# tk-retrofit.net
KiCad netlist of a schematic drawn in EAGLE
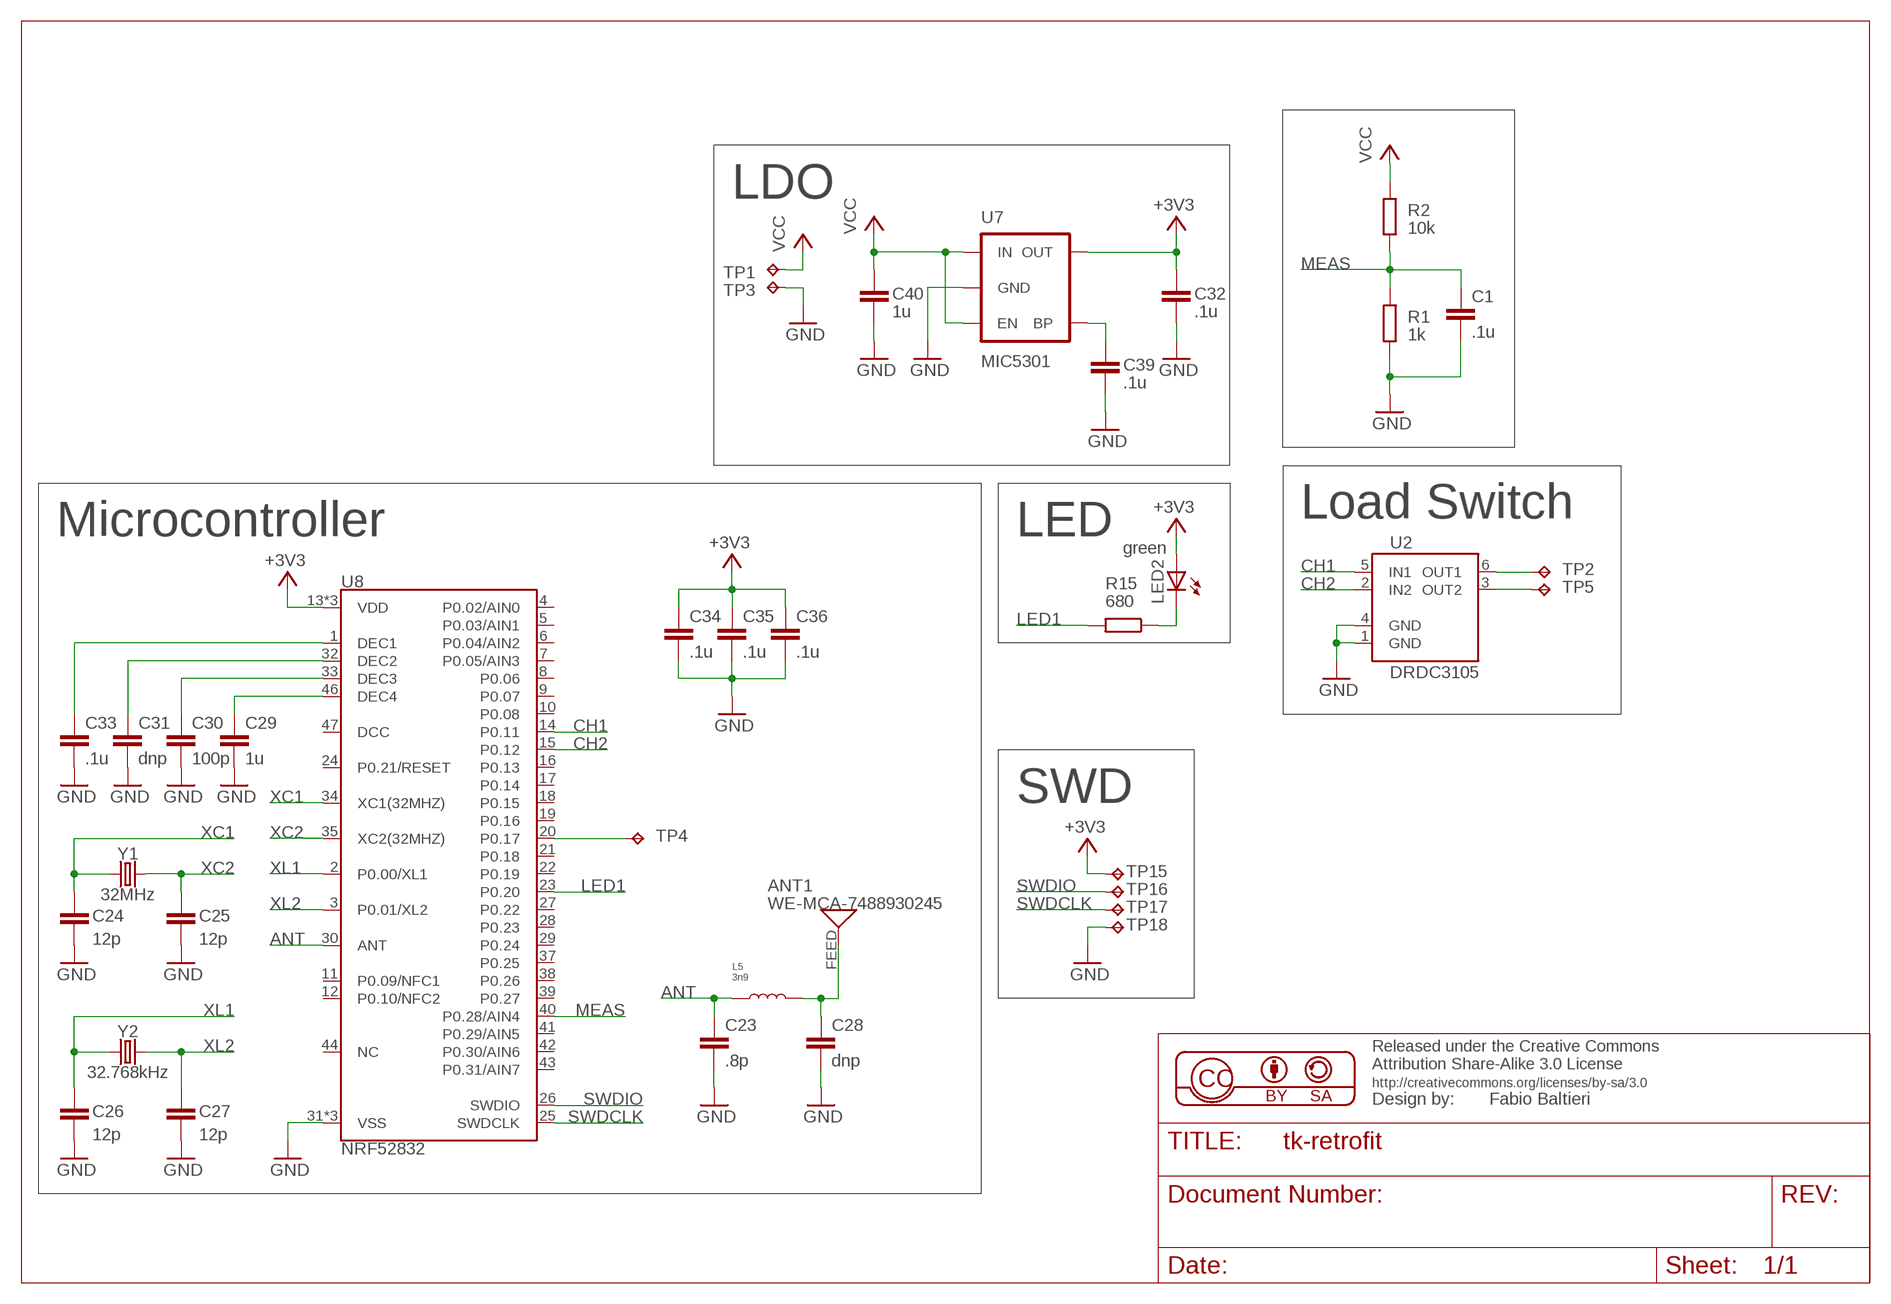
[diagram p0: schematic, sheet 1]

(export (version "E")
  (design (tool "Eeschema 10.0.6"))
  (components
    (comp (ref "ANT1")
      (value "WE-MCA-7488930245")
      (footprint "eagle-import:WE-MCA")
      (libsource (lib "eagle-import") (part "WE-MCA-7488930245"))
    )
    (comp (ref "C1")
      (value ".1u")
      (footprint "eagle-import:0603")
      (libsource (lib "eagle-import") (part "C0603"))
    )
    (comp (ref "C23")
      (value ".8p")
      (footprint "eagle-import:0603")
      (libsource (lib "eagle-import") (part "C0603"))
    )
    (comp (ref "C24")
      (value "12p")
      (footprint "eagle-import:0603")
      (libsource (lib "eagle-import") (part "C0603"))
    )
    (comp (ref "C25")
      (value "12p")
      (footprint "eagle-import:0603")
      (libsource (lib "eagle-import") (part "C0603"))
    )
    (comp (ref "C26")
      (value "12p")
      (footprint "eagle-import:0603")
      (libsource (lib "eagle-import") (part "C0603"))
    )
    (comp (ref "C27")
      (value "12p")
      (footprint "eagle-import:0603")
      (libsource (lib "eagle-import") (part "C0603"))
    )
    (comp (ref "C28")
      (value "dnp")
      (footprint "eagle-import:0603")
      (libsource (lib "eagle-import") (part "C0603"))
    )
    (comp (ref "C29")
      (value "1u")
      (footprint "eagle-import:0603")
      (libsource (lib "eagle-import") (part "C0603"))
    )
    (comp (ref "C30")
      (value "100p")
      (footprint "eagle-import:0603")
      (libsource (lib "eagle-import") (part "C0603"))
    )
    (comp (ref "C31")
      (value "dnp")
      (footprint "eagle-import:0603")
      (libsource (lib "eagle-import") (part "C0603"))
    )
    (comp (ref "C32")
      (value ".1u")
      (footprint "eagle-import:0603")
      (libsource (lib "eagle-import") (part "C0603"))
    )
    (comp (ref "C33")
      (value ".1u")
      (footprint "eagle-import:0603")
      (libsource (lib "eagle-import") (part "C0603"))
    )
    (comp (ref "C34")
      (value ".1u")
      (footprint "eagle-import:0603")
      (libsource (lib "eagle-import") (part "C0603"))
    )
    (comp (ref "C35")
      (value ".1u")
      (footprint "eagle-import:0603")
      (libsource (lib "eagle-import") (part "C0603"))
    )
    (comp (ref "C36")
      (value ".1u")
      (footprint "eagle-import:0603")
      (libsource (lib "eagle-import") (part "C0603"))
    )
    (comp (ref "C39")
      (value ".1u")
      (footprint "eagle-import:0603")
      (libsource (lib "eagle-import") (part "C0603"))
    )
    (comp (ref "C40")
      (value "1u")
      (footprint "eagle-import:0603")
      (libsource (lib "eagle-import") (part "C0603"))
    )
    (comp (ref "L5")
      (value "3n9")
      (footprint "eagle-import:L0603")
      (libsource (lib "eagle-import") (part "INDUCTOR_0603"))
    )
    (comp (ref "LED2")
      (value "LEDSML0805")
      (footprint "eagle-import:SML0805")
      (libsource (lib "eagle-import") (part "LEDSML0805"))
    )
    (comp (ref "R1")
      (value "1k")
      (footprint "eagle-import:0603")
      (libsource (lib "eagle-import") (part "R0603"))
    )
    (comp (ref "R2")
      (value "10k")
      (footprint "eagle-import:0603")
      (libsource (lib "eagle-import") (part "R0603"))
    )
    (comp (ref "R15")
      (value "680")
      (footprint "eagle-import:0603")
      (libsource (lib "eagle-import") (part "R0603"))
    )
    (comp (ref "TP1")
      (value "TPTP12R")
      (footprint "eagle-import:TP12R")
      (libsource (lib "eagle-import") (part "TPTP12R"))
    )
    (comp (ref "TP2")
      (value "TPTP12R")
      (footprint "eagle-import:TP12R")
      (libsource (lib "eagle-import") (part "TPTP12R"))
    )
    (comp (ref "TP3")
      (value "TPTP12R")
      (footprint "eagle-import:TP12R")
      (libsource (lib "eagle-import") (part "TPTP12R"))
    )
    (comp (ref "TP4")
      (value "TPTP12R")
      (footprint "eagle-import:TP12R")
      (libsource (lib "eagle-import") (part "TPTP12R"))
    )
    (comp (ref "TP5")
      (value "TPTP12R")
      (footprint "eagle-import:TP12R")
      (libsource (lib "eagle-import") (part "TPTP12R"))
    )
    (comp (ref "TP15")
      (value "TPTP12R")
      (footprint "eagle-import:TP12R")
      (libsource (lib "eagle-import") (part "TPTP12R"))
    )
    (comp (ref "TP16")
      (value "TPTP12R")
      (footprint "eagle-import:TP12R")
      (libsource (lib "eagle-import") (part "TPTP12R"))
    )
    (comp (ref "TP17")
      (value "TPTP12R")
      (footprint "eagle-import:TP12R")
      (libsource (lib "eagle-import") (part "TPTP12R"))
    )
    (comp (ref "TP18")
      (value "TPTP12R")
      (footprint "eagle-import:TP12R")
      (libsource (lib "eagle-import") (part "TPTP12R"))
    )
    (comp (ref "U2")
      (value "DRDC3105")
      (footprint "eagle-import:SOT23-6L")
      (libsource (lib "eagle-import") (part "DRDC3105"))
    )
    (comp (ref "U7")
      (value "MIC5301")
      (footprint "eagle-import:SOT23-5")
      (libsource (lib "eagle-import") (part "V_REG_LDOSMD"))
    )
    (comp (ref "U8")
      (value "NRF52832")
      (footprint "eagle-import:QFN48-6X6MM")
      (libsource (lib "eagle-import") (part "NRF52832"))
    )
    (comp (ref "Y1")
      (value "32MHz")
      (footprint "eagle-import:CRYSTAL-SMD-3.2X2.5MM")
      (libsource (lib "eagle-import") (part "CRYSTALSMD-3.2X2.5"))
    )
    (comp (ref "Y2")
      (value "32.768kHz")
      (footprint "eagle-import:CRYSTAL-SMD-3.2X1.5MM")
      (libsource (lib "eagle-import") (part "CRYSTAL-32.768KHZSMD-3.2X1.5"))
    )
  )
  (nets
    (net (code "1") (name "+3V3") (class "Default")
      (node (ref "C32") (pin "1") (pinfunction "1_1") (pintype "passive"))
      (node (ref "C34") (pin "1") (pinfunction "1_1") (pintype "passive"))
      (node (ref "C35") (pin "1") (pinfunction "1_1") (pintype "passive"))
      (node (ref "C36") (pin "1") (pinfunction "1_1") (pintype "passive"))
      (node (ref "LED2") (pin "A") (pinfunction "A_A") (pintype "passive"))
      (node (ref "TP15") (pin "TP") (pinfunction "TP_TP") (pintype "input"))
      (node (ref "U7") (pin "5") (pinfunction "OUT_5") (pintype "passive"))
      (node (ref "U8") (pin "13") (pinfunction "VDD_13") (pintype "bidirectional"))
      (node (ref "U8") (pin "36") (pinfunction "VDD_36") (pintype "bidirectional"))
      (node (ref "U8") (pin "48") (pinfunction "VDD_48") (pintype "bidirectional"))
    )
    (net (code "2") (name "/ANT") (class "Default")
      (node (ref "C23") (pin "1") (pinfunction "1_1") (pintype "passive"))
      (node (ref "L5") (pin "P$1") (pinfunction "P$1_P$1") (pintype "passive"))
      (node (ref "U8") (pin "30") (pinfunction "ANT_30") (pintype "bidirectional"))
    )
    (net (code "3") (name "/CH1") (class "Default")
      (node (ref "U2") (pin "5") (pinfunction "IN1_5") (pintype "bidirectional"))
      (node (ref "U8") (pin "14") (pinfunction "P0.11_14") (pintype "bidirectional"))
    )
    (net (code "4") (name "/CH2") (class "Default")
      (node (ref "U2") (pin "2") (pinfunction "IN2_2") (pintype "bidirectional"))
      (node (ref "U8") (pin "15") (pinfunction "P0.12_15") (pintype "bidirectional"))
    )
    (net (code "5") (name "/LED1") (class "Default")
      (node (ref "R15") (pin "2") (pinfunction "2_2") (pintype "passive"))
      (node (ref "U8") (pin "23") (pinfunction "P0.20_23") (pintype "bidirectional"))
    )
    (net (code "6") (name "/MEAS") (class "Default")
      (node (ref "C1") (pin "1") (pinfunction "1_1") (pintype "passive"))
      (node (ref "R1") (pin "1") (pinfunction "1_1") (pintype "passive"))
      (node (ref "R2") (pin "2") (pinfunction "2_2") (pintype "passive"))
      (node (ref "U8") (pin "40") (pinfunction "P0.28/AIN4_40") (pintype "bidirectional"))
    )
    (net (code "7") (name "/SWDCLK") (class "Default")
      (node (ref "TP17") (pin "TP") (pinfunction "TP_TP") (pintype "input"))
      (node (ref "U8") (pin "25") (pinfunction "SWDCLK_25") (pintype "bidirectional"))
    )
    (net (code "8") (name "/SWDIO") (class "Default")
      (node (ref "TP16") (pin "TP") (pinfunction "TP_TP") (pintype "input"))
      (node (ref "U8") (pin "26") (pinfunction "SWDIO_26") (pintype "bidirectional"))
    )
    (net (code "9") (name "/XC1") (class "Default")
      (node (ref "C24") (pin "1") (pinfunction "1_1") (pintype "passive"))
      (node (ref "U8") (pin "34") (pinfunction "XC1(32MHZ)_34") (pintype "bidirectional"))
      (node (ref "Y1") (pin "1") (pinfunction "1_1") (pintype "passive"))
    )
    (net (code "10") (name "/XC2") (class "Default")
      (node (ref "C25") (pin "1") (pinfunction "1_1") (pintype "passive"))
      (node (ref "U8") (pin "35") (pinfunction "XC2(32MHZ)_35") (pintype "bidirectional"))
      (node (ref "Y1") (pin "3") (pinfunction "2_3") (pintype "passive"))
    )
    (net (code "11") (name "/XL1") (class "Default")
      (node (ref "C26") (pin "1") (pinfunction "1_1") (pintype "passive"))
      (node (ref "U8") (pin "2") (pinfunction "P0.00/XL1_2") (pintype "bidirectional"))
      (node (ref "Y2") (pin "P$1") (pinfunction "1_P$1") (pintype "passive"))
    )
    (net (code "12") (name "/XL2") (class "Default")
      (node (ref "C27") (pin "1") (pinfunction "1_1") (pintype "passive"))
      (node (ref "U8") (pin "3") (pinfunction "P0.01/XL2_3") (pintype "bidirectional"))
      (node (ref "Y2") (pin "P$2") (pinfunction "2_P$2") (pintype "passive"))
    )
    (net (code "13") (name "GND") (class "Default")
      (node (ref "C1") (pin "2") (pinfunction "2_2") (pintype "passive"))
      (node (ref "C23") (pin "2") (pinfunction "2_2") (pintype "passive"))
      (node (ref "C24") (pin "2") (pinfunction "2_2") (pintype "passive"))
      (node (ref "C25") (pin "2") (pinfunction "2_2") (pintype "passive"))
      (node (ref "C26") (pin "2") (pinfunction "2_2") (pintype "passive"))
      (node (ref "C27") (pin "2") (pinfunction "2_2") (pintype "passive"))
      (node (ref "C28") (pin "2") (pinfunction "2_2") (pintype "passive"))
      (node (ref "C29") (pin "2") (pinfunction "2_2") (pintype "passive"))
      (node (ref "C30") (pin "2") (pinfunction "2_2") (pintype "passive"))
      (node (ref "C31") (pin "2") (pinfunction "2_2") (pintype "passive"))
      (node (ref "C32") (pin "2") (pinfunction "2_2") (pintype "passive"))
      (node (ref "C33") (pin "2") (pinfunction "2_2") (pintype "passive"))
      (node (ref "C34") (pin "2") (pinfunction "2_2") (pintype "passive"))
      (node (ref "C35") (pin "2") (pinfunction "2_2") (pintype "passive"))
      (node (ref "C36") (pin "2") (pinfunction "2_2") (pintype "passive"))
      (node (ref "C39") (pin "2") (pinfunction "2_2") (pintype "passive"))
      (node (ref "C40") (pin "2") (pinfunction "2_2") (pintype "passive"))
      (node (ref "R1") (pin "2") (pinfunction "2_2") (pintype "passive"))
      (node (ref "TP18") (pin "TP") (pinfunction "TP_TP") (pintype "input"))
      (node (ref "TP3") (pin "TP") (pinfunction "TP_TP") (pintype "input"))
      (node (ref "U2") (pin "1") (pinfunction "GND_1") (pintype "bidirectional"))
      (node (ref "U2") (pin "4") (pinfunction "GND_4") (pintype "bidirectional"))
      (node (ref "U7") (pin "2") (pinfunction "GND_2") (pintype "input"))
      (node (ref "U8") (pin "31") (pinfunction "VSS_31") (pintype "bidirectional"))
      (node (ref "U8") (pin "45") (pinfunction "VSS_45") (pintype "bidirectional"))
      (node (ref "U8") (pin "EP") (pinfunction "VSS_EP") (pintype "bidirectional"))
    )
    (net (code "14") (name "Net-(ANT1-P$1)") (class "Default")
      (node (ref "ANT1") (pin "FEED") (pinfunction "P$1_FEED") (pintype "bidirectional"))
      (node (ref "C28") (pin "1") (pinfunction "1_1") (pintype "passive"))
      (node (ref "L5") (pin "P$2") (pinfunction "P$2_P$2") (pintype "passive"))
    )
    (net (code "15") (name "Net-(LED2-PadC)") (class "Default")
      (node (ref "LED2") (pin "C") (pinfunction "C_C") (pintype "passive"))
      (node (ref "R15") (pin "1") (pinfunction "1_1") (pintype "passive"))
    )
    (net (code "16") (name "Net-(U2-OUT1)") (class "Default")
      (node (ref "TP2") (pin "TP") (pinfunction "TP_TP") (pintype "input"))
      (node (ref "U2") (pin "6") (pinfunction "OUT1_6") (pintype "bidirectional"))
    )
    (net (code "17") (name "Net-(U2-OUT2)") (class "Default")
      (node (ref "TP5") (pin "TP") (pinfunction "TP_TP") (pintype "input"))
      (node (ref "U2") (pin "3") (pinfunction "OUT2_3") (pintype "bidirectional"))
    )
    (net (code "18") (name "Net-(U7-BP)") (class "Default")
      (node (ref "C39") (pin "1") (pinfunction "1_1") (pintype "passive"))
      (node (ref "U7") (pin "4") (pinfunction "BP_4") (pintype "input"))
    )
    (net (code "19") (name "Net-(U8-DEC1)") (class "Default")
      (node (ref "C33") (pin "1") (pinfunction "1_1") (pintype "passive"))
      (node (ref "U8") (pin "1") (pinfunction "DEC1_1") (pintype "bidirectional"))
    )
    (net (code "20") (name "Net-(U8-DEC2)") (class "Default")
      (node (ref "C31") (pin "1") (pinfunction "1_1") (pintype "passive"))
      (node (ref "U8") (pin "32") (pinfunction "DEC2_32") (pintype "bidirectional"))
    )
    (net (code "21") (name "Net-(U8-DEC3)") (class "Default")
      (node (ref "C30") (pin "1") (pinfunction "1_1") (pintype "passive"))
      (node (ref "U8") (pin "33") (pinfunction "DEC3_33") (pintype "bidirectional"))
    )
    (net (code "22") (name "Net-(U8-DEC4)") (class "Default")
      (node (ref "C29") (pin "1") (pinfunction "1_1") (pintype "passive"))
      (node (ref "U8") (pin "46") (pinfunction "DEC4_46") (pintype "bidirectional"))
    )
    (net (code "23") (name "Net-(U8-P0.17)") (class "Default")
      (node (ref "TP4") (pin "TP") (pinfunction "TP_TP") (pintype "input"))
      (node (ref "U8") (pin "20") (pinfunction "P0.17_20") (pintype "bidirectional"))
    )
    (net (code "24") (name "VCC") (class "Default")
      (node (ref "C40") (pin "1") (pinfunction "1_1") (pintype "passive"))
      (node (ref "R2") (pin "1") (pinfunction "1_1") (pintype "passive"))
      (node (ref "TP1") (pin "TP") (pinfunction "TP_TP") (pintype "input"))
      (node (ref "U7") (pin "1") (pinfunction "IN_1") (pintype "input"))
      (node (ref "U7") (pin "3") (pinfunction "EN_3") (pintype "input"))
    )
    (net (code "25") (name "unconnected-(U8-DCC-Pad47)") (class "Default")
      (node (ref "U8") (pin "47") (pinfunction "DCC_47") (pintype "bidirectional"))
    )
    (net (code "26") (name "unconnected-(U8-NC-Pad44)") (class "Default")
      (node (ref "U8") (pin "44") (pinfunction "NC_44") (pintype "bidirectional"))
    )
    (net (code "27") (name "unconnected-(U8-P0.02{slash}AIN0-Pad4)") (class "Default")
      (node (ref "U8") (pin "4") (pinfunction "P0.02/AIN0_4") (pintype "bidirectional"))
    )
    (net (code "28") (name "unconnected-(U8-P0.03{slash}AIN1-Pad5)") (class "Default")
      (node (ref "U8") (pin "5") (pinfunction "P0.03/AIN1_5") (pintype "bidirectional"))
    )
    (net (code "29") (name "unconnected-(U8-P0.04{slash}AIN2-Pad6)") (class "Default")
      (node (ref "U8") (pin "6") (pinfunction "P0.04/AIN2_6") (pintype "bidirectional"))
    )
    (net (code "30") (name "unconnected-(U8-P0.05{slash}AIN3-Pad7)") (class "Default")
      (node (ref "U8") (pin "7") (pinfunction "P0.05/AIN3_7") (pintype "bidirectional"))
    )
    (net (code "31") (name "unconnected-(U8-P0.06-Pad8)") (class "Default")
      (node (ref "U8") (pin "8") (pinfunction "P0.06_8") (pintype "bidirectional"))
    )
    (net (code "32") (name "unconnected-(U8-P0.07-Pad9)") (class "Default")
      (node (ref "U8") (pin "9") (pinfunction "P0.07_9") (pintype "bidirectional"))
    )
    (net (code "33") (name "unconnected-(U8-P0.08-Pad10)") (class "Default")
      (node (ref "U8") (pin "10") (pinfunction "P0.08_10") (pintype "bidirectional"))
    )
    (net (code "34") (name "unconnected-(U8-P0.09{slash}NFC1-Pad11)") (class "Default")
      (node (ref "U8") (pin "11") (pinfunction "P0.09/NFC1_11") (pintype "bidirectional"))
    )
    (net (code "35") (name "unconnected-(U8-P0.10{slash}NFC2-Pad12)") (class "Default")
      (node (ref "U8") (pin "12") (pinfunction "P0.10/NFC2_12") (pintype "bidirectional"))
    )
    (net (code "36") (name "unconnected-(U8-P0.13-Pad16)") (class "Default")
      (node (ref "U8") (pin "16") (pinfunction "P0.13_16") (pintype "bidirectional"))
    )
    (net (code "37") (name "unconnected-(U8-P0.14-Pad17)") (class "Default")
      (node (ref "U8") (pin "17") (pinfunction "P0.14_17") (pintype "bidirectional"))
    )
    (net (code "38") (name "unconnected-(U8-P0.15-Pad18)") (class "Default")
      (node (ref "U8") (pin "18") (pinfunction "P0.15_18") (pintype "bidirectional"))
    )
    (net (code "39") (name "unconnected-(U8-P0.16-Pad19)") (class "Default")
      (node (ref "U8") (pin "19") (pinfunction "P0.16_19") (pintype "bidirectional"))
    )
    (net (code "40") (name "unconnected-(U8-P0.18-Pad21)") (class "Default")
      (node (ref "U8") (pin "21") (pinfunction "P0.18_21") (pintype "bidirectional"))
    )
    (net (code "41") (name "unconnected-(U8-P0.19-Pad22)") (class "Default")
      (node (ref "U8") (pin "22") (pinfunction "P0.19_22") (pintype "bidirectional"))
    )
    (net (code "42") (name "unconnected-(U8-P0.21{slash}RESET-Pad24)") (class "Default")
      (node (ref "U8") (pin "24") (pinfunction "P0.21/RESET_24") (pintype "bidirectional"))
    )
    (net (code "43") (name "unconnected-(U8-P0.22-Pad27)") (class "Default")
      (node (ref "U8") (pin "27") (pinfunction "P0.22_27") (pintype "bidirectional"))
    )
    (net (code "44") (name "unconnected-(U8-P0.23-Pad28)") (class "Default")
      (node (ref "U8") (pin "28") (pinfunction "P0.23_28") (pintype "bidirectional"))
    )
    (net (code "45") (name "unconnected-(U8-P0.24-Pad29)") (class "Default")
      (node (ref "U8") (pin "29") (pinfunction "P0.24_29") (pintype "bidirectional"))
    )
    (net (code "46") (name "unconnected-(U8-P0.25-Pad37)") (class "Default")
      (node (ref "U8") (pin "37") (pinfunction "P0.25_37") (pintype "bidirectional"))
    )
    (net (code "47") (name "unconnected-(U8-P0.26-Pad38)") (class "Default")
      (node (ref "U8") (pin "38") (pinfunction "P0.26_38") (pintype "bidirectional"))
    )
    (net (code "48") (name "unconnected-(U8-P0.27-Pad39)") (class "Default")
      (node (ref "U8") (pin "39") (pinfunction "P0.27_39") (pintype "bidirectional"))
    )
    (net (code "49") (name "unconnected-(U8-P0.29{slash}AIN5-Pad41)") (class "Default")
      (node (ref "U8") (pin "41") (pinfunction "P0.29/AIN5_41") (pintype "bidirectional"))
    )
    (net (code "50") (name "unconnected-(U8-P0.30{slash}AIN6-Pad42)") (class "Default")
      (node (ref "U8") (pin "42") (pinfunction "P0.30/AIN6_42") (pintype "bidirectional"))
    )
    (net (code "51") (name "unconnected-(U8-P0.31{slash}AIN7-Pad43)") (class "Default")
      (node (ref "U8") (pin "43") (pinfunction "P0.31/AIN7_43") (pintype "bidirectional"))
    )
  )
)
